# MODEM_R2_1.net
KiCad netlist of a schematic drawn in Altium Designer
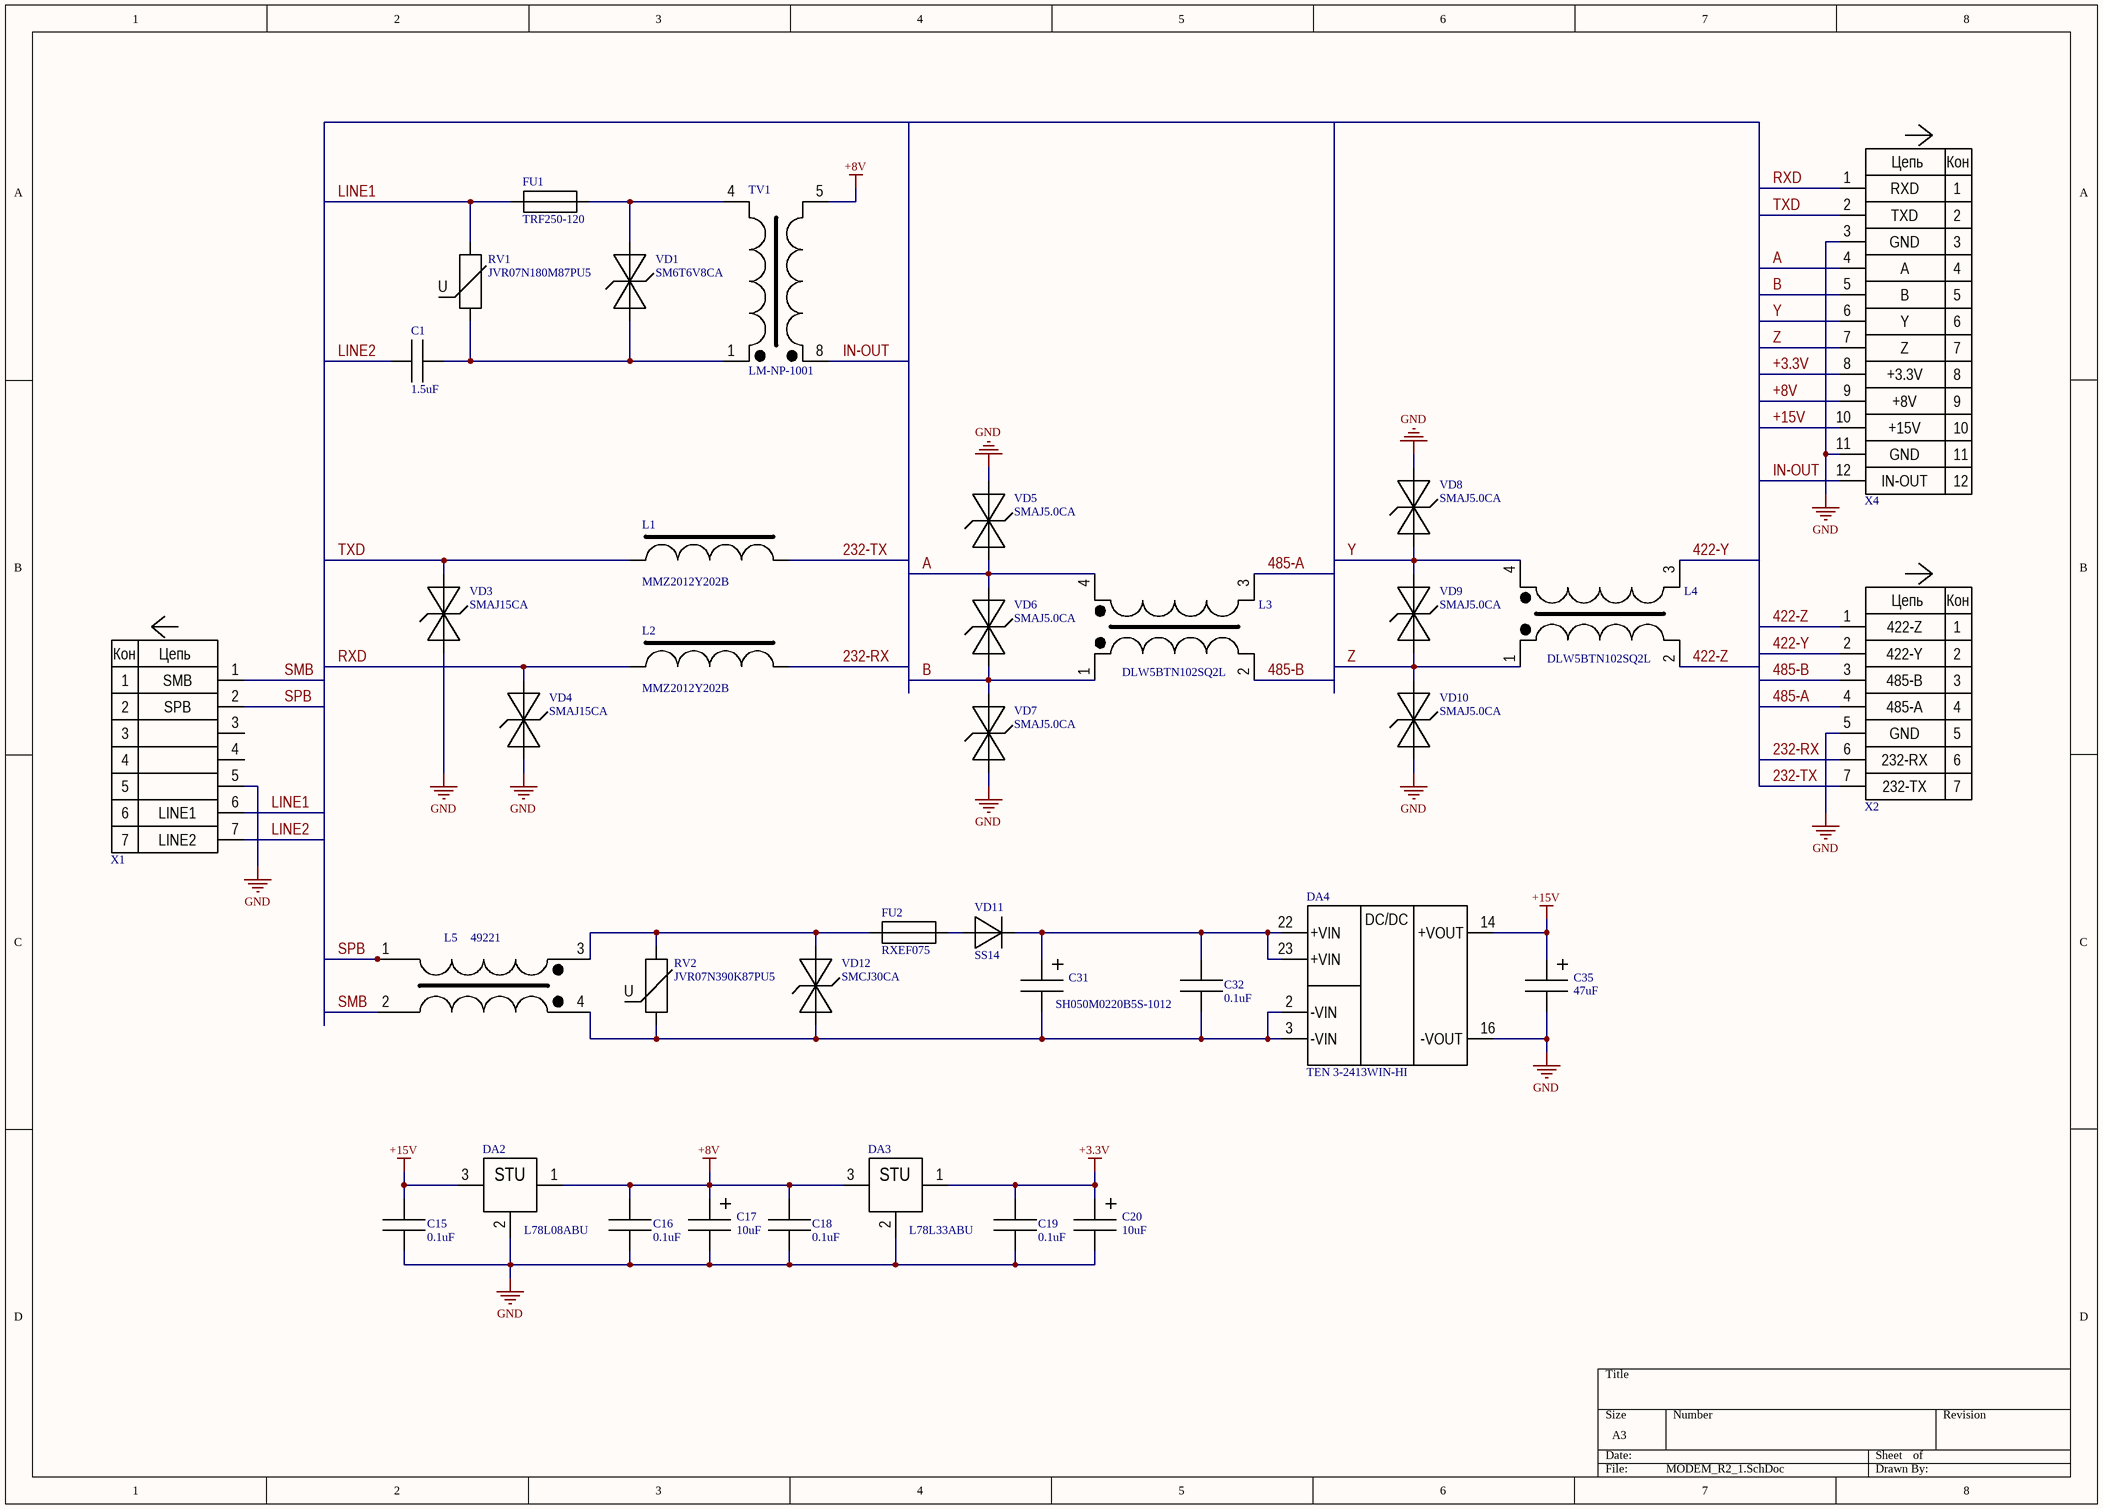
[diagram p0: MODEM_R2_1.SchDoc]

(export (version "E")
  (design (tool "Eeschema 10.0.6"))
  (components
    (comp (ref "C1") (value "1.5uF") (footprint "TS02-22.5-h") (libsource (lib "CAPACITORS") (part "CC1206")))
    (comp (ref "C15") (value "0.1uF") (footprint "CC0805") (libsource (lib "CAPACITORS") (part "CC1206")))
    (comp (ref "C16") (value "0.1uF") (footprint "CC0805") (libsource (lib "CAPACITORS") (part "CC1206")))
    (comp (ref "C17") (value "10uF") (footprint "SMB") (libsource (lib "CAPACITORS") (part "SR-6")))
    (comp (ref "C18") (value "0.1uF") (footprint "CC0805") (libsource (lib "CAPACITORS") (part "CC1206")))
    (comp (ref "C19") (value "0.1uF") (footprint "CC0805") (libsource (lib "CAPACITORS") (part "CC1206")))
    (comp (ref "C20") (value "10uF") (footprint "SMB") (libsource (lib "CAPACITORS") (part "SR-6")))
    (comp (ref "C31")
      (value "SH050M0220B5S-1012")
      (footprint "Discr:SH050-1019")
      (libsource (lib "CAPACITORS") (part "SR-6"))
    )
    (comp (ref "C32") (value "0.1uF") (footprint "CC0805") (libsource (lib "CAPACITORS") (part "CC1206")))
    (comp (ref "C35") (value "47uF") (footprint "SMD") (libsource (lib "CAPACITORS") (part "SR-6")))
    (comp (ref "DA2") (value "L78L08ABU") (footprint "SOT-89") (libsource (lib "IC") (part "L78L08ABU")))
    (comp (ref "DA3") (value "L78L33ABU") (footprint "SOT-89") (libsource (lib "IC") (part "L78L33ABU")))
    (comp (ref "DA4")
      (value "TEN 3-2413WIN-HI")
      (footprint "TEN3-2412WIN")
      (libsource (lib "Power Supplies") (part "TEN3-2412WIN"))
    )
    (comp (ref "FU1")
      (value "TRF250-120")
      (footprint "TRF250-120")
      (libsource (lib "Discr") (part "TRF250-120"))
    )
    (comp (ref "FU2") (value "RXEF075") (footprint "RXEF075") (libsource (lib "Discr") (part "TRF250-120")))
    (comp (ref "L1")
      (value "MMZ2012Y202B")
      (footprint "MMZ2012Y202B")
      (libsource (lib "INDUCTORS") (part "MMZ2012Y202B"))
    )
    (comp (ref "L2")
      (value "MMZ2012Y202B")
      (footprint "MMZ2012Y202B")
      (libsource (lib "INDUCTORS") (part "MMZ2012Y202B"))
    )
    (comp (ref "L3")
      (value "DLW5BTN102SQ2L")
      (footprint "DLW5BTN")
      (libsource (lib "INDUCTORS") (part "DLW31SN"))
    )
    (comp (ref "L4")
      (value "DLW5BTN102SQ2L")
      (footprint "DLW5BTN")
      (libsource (lib "INDUCTORS") (part "DLW31SN"))
    )
    (comp (ref "L5") (value "49221") (footprint "49221") (libsource (lib "INDUCTORS") (part "49221")))
    (comp (ref "RV1")
      (value "JVR07N180M87PU5")
      (footprint "JVR07N330")
      (libsource (lib "Discr") (part "JVR14N361"))
    )
    (comp (ref "RV2")
      (value "JVR07N390K87PU5")
      (footprint "JVR07N330")
      (libsource (lib "Discr") (part "JVR14N361"))
    )
    (comp (ref "TV1")
      (value "LM-NP-1001")
      (footprint "LM-NP-1001")
      (libsource (lib "INDUCTORS") (part "LM-NP-1001"))
    )
    (comp (ref "VD1")
      (value "SM6T6V8CA")
      (footprint "SM6T6V8CA")
      (libsource (lib "DIODES") (part "SM6T6V8CA"))
    )
    (comp (ref "VD3")
      (value "SMAJ15CA")
      (footprint "SMAJ6.0CA")
      (libsource (lib "DIODES") (part "SMAJ6.0CA"))
    )
    (comp (ref "VD4")
      (value "SMAJ15CA")
      (footprint "SMAJ6.0CA")
      (libsource (lib "DIODES") (part "SMAJ6.0CA"))
    )
    (comp (ref "VD5")
      (value "SMAJ5.0CA")
      (footprint "SMAJ6.0CA")
      (libsource (lib "DIODES") (part "SMAJ6.0CA"))
    )
    (comp (ref "VD6")
      (value "SMAJ5.0CA")
      (footprint "SMAJ6.0CA")
      (libsource (lib "DIODES") (part "SMAJ6.0CA"))
    )
    (comp (ref "VD7")
      (value "SMAJ5.0CA")
      (footprint "SMAJ6.0CA")
      (libsource (lib "DIODES") (part "SMAJ6.0CA"))
    )
    (comp (ref "VD8")
      (value "SMAJ5.0CA")
      (footprint "SMAJ6.0CA")
      (libsource (lib "DIODES") (part "SMAJ6.0CA"))
    )
    (comp (ref "VD9")
      (value "SMAJ5.0CA")
      (footprint "SMAJ6.0CA")
      (libsource (lib "DIODES") (part "SMAJ6.0CA"))
    )
    (comp (ref "VD10")
      (value "SMAJ5.0CA")
      (footprint "SMAJ6.0CA")
      (libsource (lib "DIODES") (part "SMAJ6.0CA"))
    )
    (comp (ref "VD11") (value "SS14") (footprint "SS14") (libsource (lib "DIODES") (part "SS14")))
    (comp (ref "VD12") (value "SMCJ30CA") (footprint "SMCJ28A") (libsource (lib "DIODES") (part "SM6T6V8CA")))
    (comp (ref "X1")
      (value "8113_S/07")
      (footprint "8113_S/07")
      (libsource (lib "COMMUT") (part "8113_S/07"))
    )
    (comp (ref "X2")
      (value "8113_S/07")
      (footprint "8113_S/07")
      (libsource (lib "COMMUT") (part "8113_S/07"))
    )
    (comp (ref "X4") (value "PLS-12") (footprint "PLS-12") (libsource (lib "COMMUT") (part "PLS-12")))
  )
  (nets
    (net (code "1") (name "+3.3V") (class "Default")
      (node (ref "C19") (pin "2") (pinfunction "2_2") (pintype "passive"))
      (node (ref "C20") (pin "2") (pinfunction "A_2") (pintype "passive"))
      (node (ref "DA3") (pin "1") (pinfunction "OUT_1") (pintype "power_in"))
      (node (ref "X4") (pin "8") (pinfunction "8_8") (pintype "passive"))
    )
    (net (code "2") (name "+8V") (class "Default")
      (node (ref "C16") (pin "2") (pinfunction "2_2") (pintype "passive"))
      (node (ref "C17") (pin "2") (pinfunction "A_2") (pintype "passive"))
      (node (ref "C18") (pin "2") (pinfunction "2_2") (pintype "passive"))
      (node (ref "DA2") (pin "1") (pinfunction "OUT_1") (pintype "power_in"))
      (node (ref "DA3") (pin "3") (pinfunction "IN_3") (pintype "power_in"))
      (node (ref "TV1") (pin "5") (pinfunction "5_5") (pintype "passive"))
      (node (ref "X4") (pin "9") (pinfunction "9_9") (pintype "passive"))
    )
    (net (code "3") (name "+15V") (class "Default")
      (node (ref "C15") (pin "2") (pinfunction "2_2") (pintype "passive"))
      (node (ref "C35") (pin "2") (pinfunction "A_2") (pintype "passive"))
      (node (ref "DA2") (pin "3") (pinfunction "IN_3") (pintype "power_in"))
      (node (ref "DA4") (pin "14") (pinfunction "+VOUT_14") (pintype "power_in"))
      (node (ref "X4") (pin "10") (pinfunction "10_10") (pintype "passive"))
    )
    (net (code "4") (name "/232-RX") (class "Default")
      (node (ref "L2") (pin "2") (pinfunction "2_2") (pintype "passive"))
      (node (ref "X2") (pin "6") (pinfunction "6_6") (pintype "passive"))
    )
    (net (code "5") (name "/232-TX") (class "Default")
      (node (ref "L1") (pin "2") (pinfunction "2_2") (pintype "passive"))
      (node (ref "X2") (pin "7") (pinfunction "7_7") (pintype "passive"))
    )
    (net (code "6") (name "/422-Y") (class "Default")
      (node (ref "L4") (pin "3") (pinfunction "3_3") (pintype "passive"))
      (node (ref "X2") (pin "2") (pinfunction "2_2") (pintype "passive"))
    )
    (net (code "7") (name "/422-Z") (class "Default")
      (node (ref "L4") (pin "2") (pinfunction "2_2") (pintype "passive"))
      (node (ref "X2") (pin "1") (pinfunction "1_1") (pintype "passive"))
    )
    (net (code "8") (name "/485-A") (class "Default")
      (node (ref "L3") (pin "3") (pinfunction "3_3") (pintype "passive"))
      (node (ref "X2") (pin "4") (pinfunction "4_4") (pintype "passive"))
    )
    (net (code "9") (name "/485-B") (class "Default")
      (node (ref "L3") (pin "2") (pinfunction "2_2") (pintype "passive"))
      (node (ref "X2") (pin "3") (pinfunction "3_3") (pintype "passive"))
    )
    (net (code "10") (name "/A") (class "Default")
      (node (ref "L3") (pin "4") (pinfunction "4_4") (pintype "passive"))
      (node (ref "VD5") (pin "1") (pinfunction "A_1") (pintype "passive"))
      (node (ref "VD6") (pin "2") (pinfunction "С_2") (pintype "passive"))
      (node (ref "X4") (pin "4") (pinfunction "4_4") (pintype "passive"))
    )
    (net (code "11") (name "/B") (class "Default")
      (node (ref "L3") (pin "1") (pinfunction "1_1") (pintype "passive"))
      (node (ref "VD6") (pin "1") (pinfunction "A_1") (pintype "passive"))
      (node (ref "VD7") (pin "2") (pinfunction "С_2") (pintype "passive"))
      (node (ref "X4") (pin "5") (pinfunction "5_5") (pintype "passive"))
    )
    (net (code "12") (name "/IN-OUT") (class "Default")
      (node (ref "TV1") (pin "8") (pinfunction "8_8") (pintype "passive"))
      (node (ref "X4") (pin "12") (pinfunction "12_12") (pintype "passive"))
    )
    (net (code "13") (name "/LINE1") (class "Default")
      (node (ref "FU1") (pin "1") (pinfunction "1_1") (pintype "passive"))
      (node (ref "RV1") (pin "1") (pinfunction "1_1") (pintype "passive"))
      (node (ref "X1") (pin "6") (pinfunction "6_6") (pintype "passive"))
    )
    (net (code "14") (name "/LINE2") (class "Default")
      (node (ref "C1") (pin "1") (pinfunction "1_1") (pintype "passive"))
      (node (ref "X1") (pin "7") (pinfunction "7_7") (pintype "passive"))
    )
    (net (code "15") (name "/RXD") (class "Default")
      (node (ref "L2") (pin "1") (pinfunction "1_1") (pintype "passive"))
      (node (ref "VD4") (pin "2") (pinfunction "С_2") (pintype "passive"))
      (node (ref "X4") (pin "1") (pinfunction "1_1") (pintype "passive"))
    )
    (net (code "16") (name "/SMB") (class "Default")
      (node (ref "L5") (pin "2") (pinfunction "2_2") (pintype "passive"))
      (node (ref "X1") (pin "1") (pinfunction "1_1") (pintype "passive"))
    )
    (net (code "17") (name "/SPB") (class "Default")
      (node (ref "L5") (pin "1") (pinfunction "1_1") (pintype "passive"))
      (node (ref "X1") (pin "2") (pinfunction "2_2") (pintype "passive"))
    )
    (net (code "18") (name "/TXD") (class "Default")
      (node (ref "L1") (pin "1") (pinfunction "1_1") (pintype "passive"))
      (node (ref "VD3") (pin "2") (pinfunction "С_2") (pintype "passive"))
      (node (ref "X4") (pin "2") (pinfunction "2_2") (pintype "passive"))
    )
    (net (code "19") (name "/Y") (class "Default")
      (node (ref "L4") (pin "4") (pinfunction "4_4") (pintype "passive"))
      (node (ref "VD8") (pin "1") (pinfunction "A_1") (pintype "passive"))
      (node (ref "VD9") (pin "2") (pinfunction "С_2") (pintype "passive"))
      (node (ref "X4") (pin "6") (pinfunction "6_6") (pintype "passive"))
    )
    (net (code "20") (name "/Z") (class "Default")
      (node (ref "L4") (pin "1") (pinfunction "1_1") (pintype "passive"))
      (node (ref "VD10") (pin "2") (pinfunction "С_2") (pintype "passive"))
      (node (ref "VD9") (pin "1") (pinfunction "A_1") (pintype "passive"))
      (node (ref "X4") (pin "7") (pinfunction "7_7") (pintype "passive"))
    )
    (net (code "21") (name "GND") (class "Default")
      (node (ref "C15") (pin "1") (pinfunction "1_1") (pintype "passive"))
      (node (ref "C16") (pin "1") (pinfunction "1_1") (pintype "passive"))
      (node (ref "C17") (pin "1") (pinfunction "C_1") (pintype "passive"))
      (node (ref "C18") (pin "1") (pinfunction "1_1") (pintype "passive"))
      (node (ref "C19") (pin "1") (pinfunction "1_1") (pintype "passive"))
      (node (ref "C20") (pin "1") (pinfunction "C_1") (pintype "passive"))
      (node (ref "C35") (pin "1") (pinfunction "C_1") (pintype "passive"))
      (node (ref "DA2") (pin "2") (pinfunction "GND_2") (pintype "power_in"))
      (node (ref "DA3") (pin "2") (pinfunction "GND_2") (pintype "power_in"))
      (node (ref "DA4") (pin "16") (pinfunction "-VOUT_16") (pintype "power_in"))
      (node (ref "VD10") (pin "1") (pinfunction "A_1") (pintype "passive"))
      (node (ref "VD3") (pin "1") (pinfunction "A_1") (pintype "passive"))
      (node (ref "VD4") (pin "1") (pinfunction "A_1") (pintype "passive"))
      (node (ref "VD5") (pin "2") (pinfunction "С_2") (pintype "passive"))
      (node (ref "VD7") (pin "1") (pinfunction "A_1") (pintype "passive"))
      (node (ref "VD8") (pin "2") (pinfunction "С_2") (pintype "passive"))
      (node (ref "X1") (pin "5") (pinfunction "5_5") (pintype "passive"))
      (node (ref "X2") (pin "5") (pinfunction "5_5") (pintype "passive"))
      (node (ref "X4") (pin "11") (pinfunction "11_11") (pintype "passive"))
      (node (ref "X4") (pin "3") (pinfunction "3_3") (pintype "passive"))
    )
    (net (code "22") (name "Net-(C31-A)") (class "Default")
      (node (ref "C31") (pin "2") (pinfunction "A_2") (pintype "passive"))
      (node (ref "C32") (pin "2") (pinfunction "2_2") (pintype "passive"))
      (node (ref "DA4") (pin "22") (pinfunction "+VIN_22") (pintype "power_in"))
      (node (ref "DA4") (pin "23") (pinfunction "+VIN_23") (pintype "power_in"))
      (node (ref "VD11") (pin "2") (pinfunction "С_2") (pintype "passive"))
    )
    (net (code "23") (name "Net-(C31-C)") (class "Default")
      (node (ref "C31") (pin "1") (pinfunction "C_1") (pintype "passive"))
      (node (ref "C32") (pin "1") (pinfunction "1_1") (pintype "passive"))
      (node (ref "DA4") (pin "2") (pinfunction "-VIN_2") (pintype "power_in"))
      (node (ref "DA4") (pin "3") (pinfunction "-VIN_3") (pintype "power_in"))
      (node (ref "L5") (pin "4") (pinfunction "4_4") (pintype "passive"))
      (node (ref "RV2") (pin "2") (pinfunction "2_2") (pintype "passive"))
      (node (ref "VD12") (pin "1") (pinfunction "A_1") (pintype "passive"))
    )
    (net (code "24") (name "Net-(VD1-A)") (class "Default")
      (node (ref "C1") (pin "2") (pinfunction "2_2") (pintype "passive"))
      (node (ref "RV1") (pin "2") (pinfunction "2_2") (pintype "passive"))
      (node (ref "TV1") (pin "1") (pinfunction "1_1") (pintype "passive"))
      (node (ref "VD1") (pin "1") (pinfunction "A_1") (pintype "passive"))
    )
    (net (code "25") (name "Net-(VD1-С)") (class "Default")
      (node (ref "FU1") (pin "2") (pinfunction "2_2") (pintype "passive"))
      (node (ref "TV1") (pin "4") (pinfunction "4_4") (pintype "passive"))
      (node (ref "VD1") (pin "2") (pinfunction "С_2") (pintype "passive"))
    )
    (net (code "26") (name "Net-(VD11-A)") (class "Default")
      (node (ref "FU2") (pin "2") (pinfunction "2_2") (pintype "passive"))
      (node (ref "VD11") (pin "1") (pinfunction "A_1") (pintype "passive"))
    )
    (net (code "27") (name "Net-(VD12-С)") (class "Default")
      (node (ref "FU2") (pin "1") (pinfunction "1_1") (pintype "passive"))
      (node (ref "L5") (pin "3") (pinfunction "3_3") (pintype "passive"))
      (node (ref "RV2") (pin "1") (pinfunction "1_1") (pintype "passive"))
      (node (ref "VD12") (pin "2") (pinfunction "С_2") (pintype "passive"))
    )
    (net (code "28") (name "unconnected-(X1-Pad3)") (class "Default")
      (node (ref "X1") (pin "3") (pinfunction "3_3") (pintype "passive"))
    )
    (net (code "29") (name "unconnected-(X1-Pad4)") (class "Default")
      (node (ref "X1") (pin "4") (pinfunction "4_4") (pintype "passive"))
    )
  )
)
